# WIFI-RF433.net
KiCad netlist of a schematic drawn in EAGLE
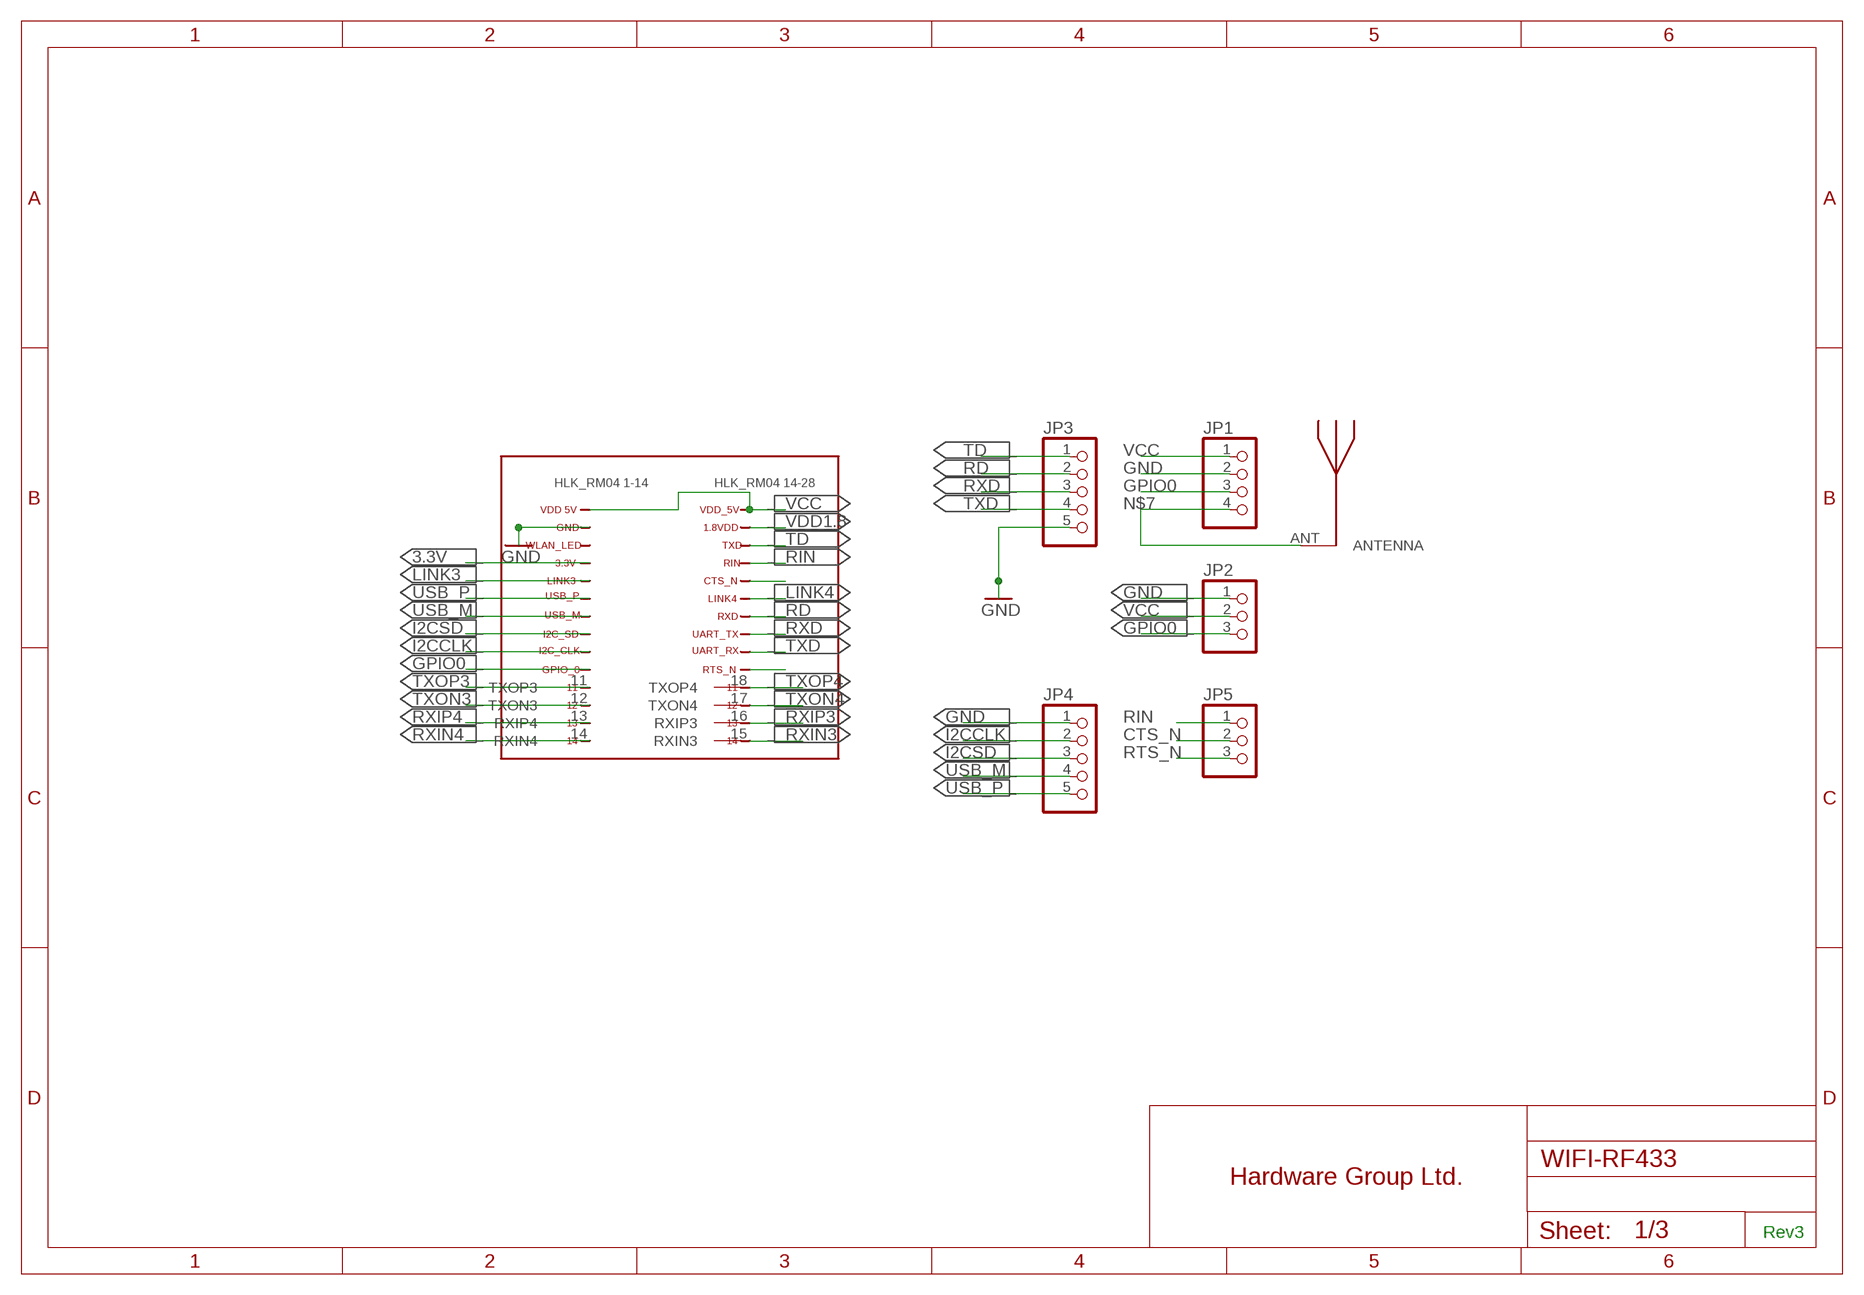
[diagram p0: schematic, sheet 1]
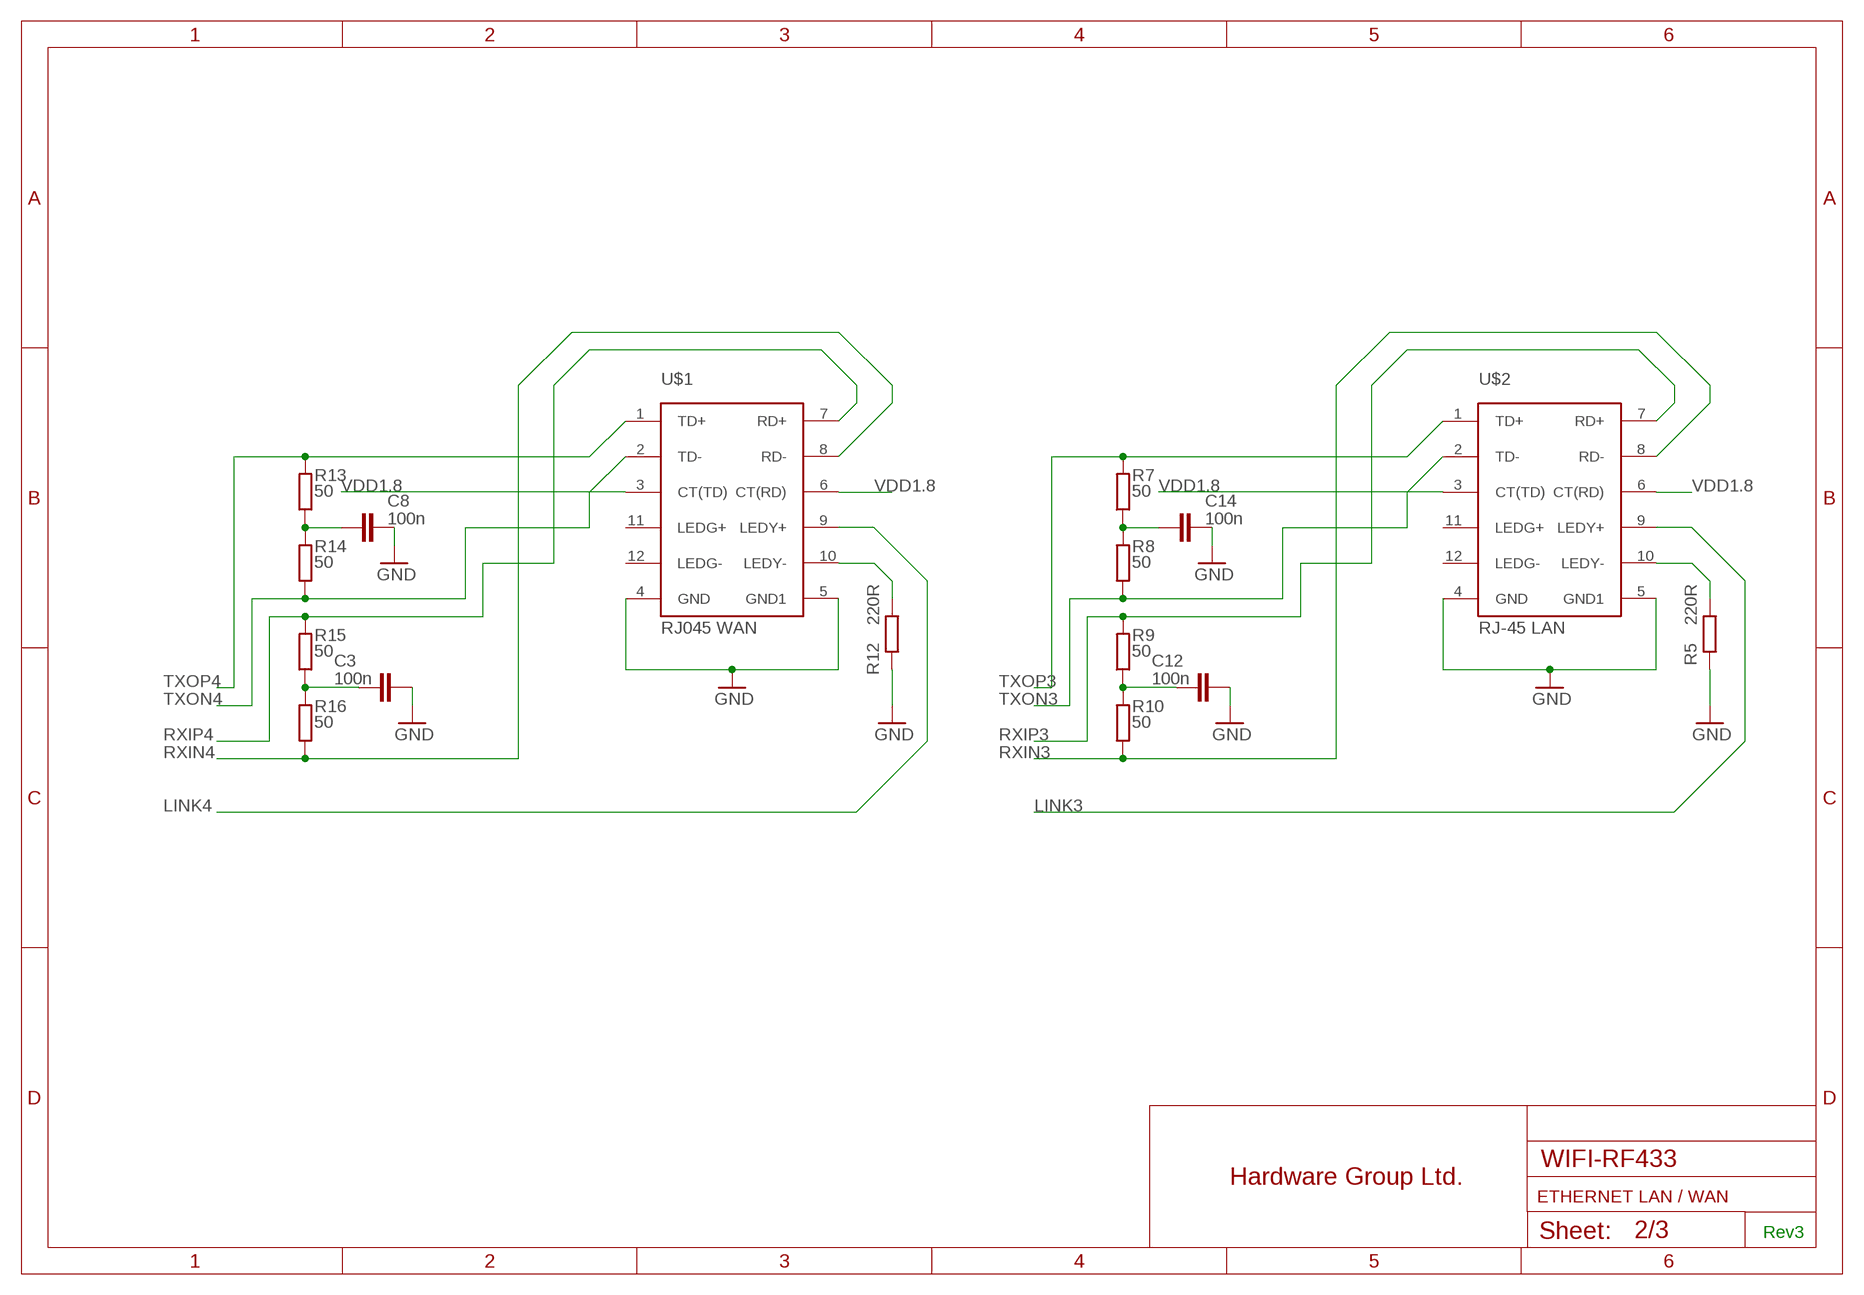
[diagram p1: schematic, sheet 2]
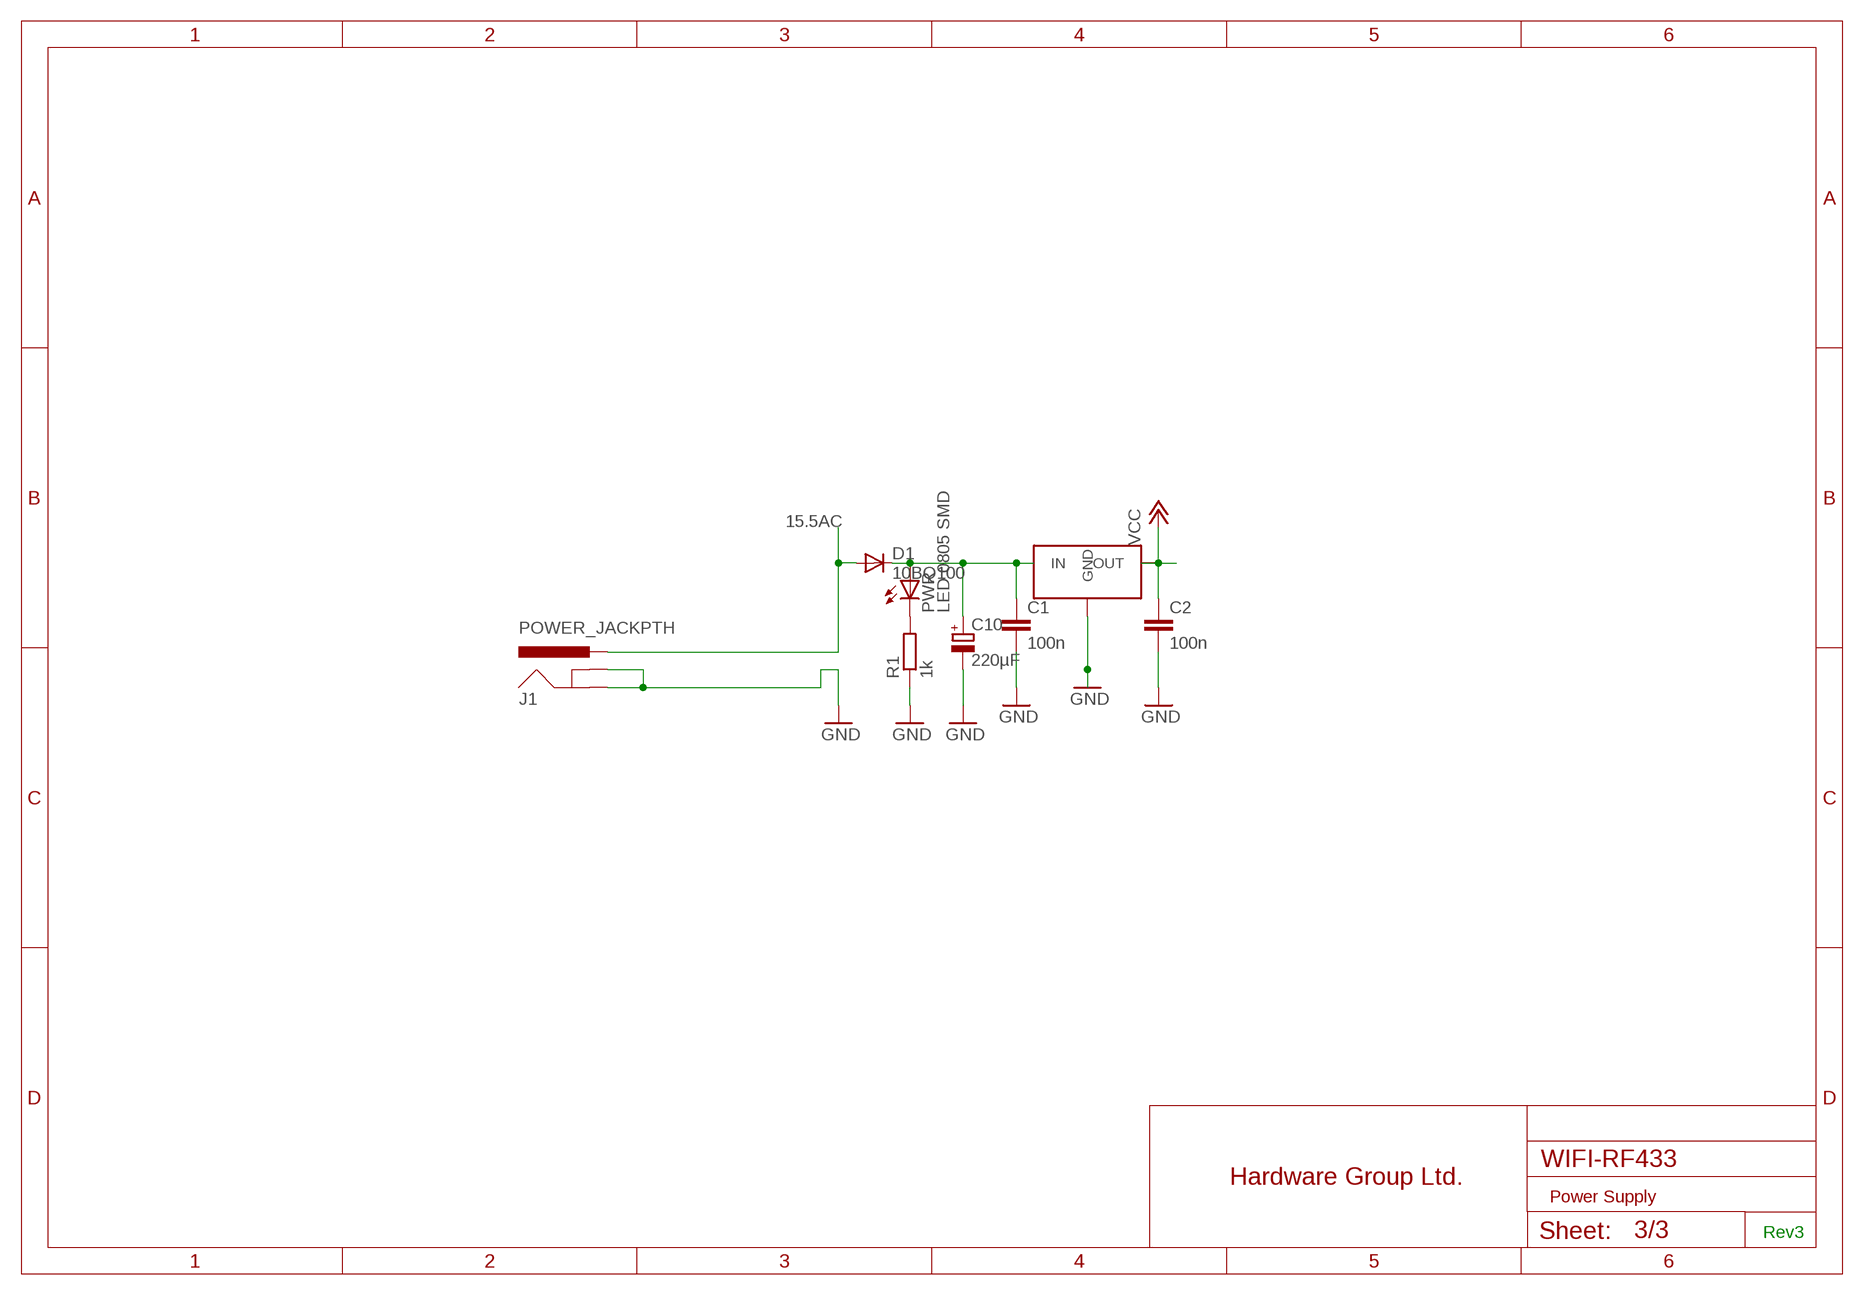
[diagram p2: schematic, sheet 3]

(export (version "E")
  (design (tool "Eeschema 10.0.6"))
  (components
    (comp (ref "C1")
      (value "100n")
      (footprint "eagle-import:C0805")
      (libsource (lib "eagle-import") (part "C-EUC0805"))
    )
    (comp (ref "C2")
      (value "100n")
      (footprint "eagle-import:C0805")
      (libsource (lib "eagle-import") (part "C-EUC0805"))
    )
    (comp (ref "C10")
      (value "220µF")
      (footprint "eagle-import:E3,5-8")
      (libsource (lib "eagle-import") (part "CPOL-EUE3.5-8"))
    )
    (comp (ref "D1")
      (value "10BQ100")
      (footprint "eagle-import:SMB")
      (libsource (lib "eagle-import") (part "DIODE-SMB"))
    )
    (comp (ref "J1")
      (value "POWER_JACKPTH")
      (footprint "eagle-import:POWER_JACK_PTH")
      (libsource (lib "eagle-import") (part "POWER_JACKPTH"))
    )
    (comp (ref "PWR")
      (value "LED 0805 SMD")
      (footprint "eagle-import:CHIP-LED0805")
      (libsource (lib "eagle-import") (part "LEDCHIP-LED0805"))
    )
    (comp (ref "R1")
      (value "1k")
      (footprint "eagle-import:M0805")
      (libsource (lib "eagle-import") (part "R-EU_M0805"))
    )
    (comp (ref "U$3")
      (value "VREG-7805-DPAK2")
      (footprint "eagle-import:VREG-7805-DPAK2")
      (libsource (lib "eagle-import") (part "VREG-7805-DPAK2"))
    )
    (comp (ref "JP1")
      (value "PINHD-1X4")
      (footprint "eagle-import:1X04")
      (libsource (lib "eagle-import") (part "PINHD-1X4"))
    )
    (comp (ref "JP2")
      (value "PINHD-1X3")
      (footprint "eagle-import:1X03")
      (libsource (lib "eagle-import") (part "PINHD-1X3"))
    )
    (comp (ref "JP3")
      (value "PINHD-1X5")
      (footprint "eagle-import:1X05")
      (libsource (lib "eagle-import") (part "PINHD-1X5"))
    )
    (comp (ref "JP4")
      (value "PINHD-1X5")
      (footprint "eagle-import:1X05")
      (libsource (lib "eagle-import") (part "PINHD-1X5"))
    )
    (comp (ref "JP5")
      (value "PINHD-1X3")
      (footprint "eagle-import:1X03")
      (libsource (lib "eagle-import") (part "PINHD-1X3"))
    )
    (comp (ref "U$4")
      (value "433MHZ")
      (footprint "eagle-import:433MHZ")
      (libsource (lib "eagle-import") (part "433MHZ"))
    )
    (comp (ref "U$8")
      (value "1X10")
      (footprint "eagle-import:1X10")
      (libsource (lib "eagle-import") (part "1X10"))
    )
    (comp (ref "C3")
      (value "100n")
      (footprint "eagle-import:C0805")
      (libsource (lib "eagle-import") (part "C-EUC0805"))
    )
    (comp (ref "C8")
      (value "100n")
      (footprint "eagle-import:C0805")
      (libsource (lib "eagle-import") (part "C-EUC0805"))
    )
    (comp (ref "C12")
      (value "100n")
      (footprint "eagle-import:C0805")
      (libsource (lib "eagle-import") (part "C-EUC0805"))
    )
    (comp (ref "C14")
      (value "100n")
      (footprint "eagle-import:C0805")
      (libsource (lib "eagle-import") (part "C-EUC0805"))
    )
    (comp (ref "R5")
      (value "220R")
      (footprint "eagle-import:R0805")
      (libsource (lib "eagle-import") (part "R-EU_R0805"))
    )
    (comp (ref "R7")
      (value "50")
      (footprint "eagle-import:R0805")
      (libsource (lib "eagle-import") (part "R-EU_R0805"))
    )
    (comp (ref "R8")
      (value "50")
      (footprint "eagle-import:R0805")
      (libsource (lib "eagle-import") (part "R-EU_R0805"))
    )
    (comp (ref "R9")
      (value "50")
      (footprint "eagle-import:R0805")
      (libsource (lib "eagle-import") (part "R-EU_R0805"))
    )
    (comp (ref "R10")
      (value "50")
      (footprint "eagle-import:R0805")
      (libsource (lib "eagle-import") (part "R-EU_R0805"))
    )
    (comp (ref "R12")
      (value "220R")
      (footprint "eagle-import:R0805")
      (libsource (lib "eagle-import") (part "R-EU_R0805"))
    )
    (comp (ref "R13")
      (value "50")
      (footprint "eagle-import:R0805")
      (libsource (lib "eagle-import") (part "R-EU_R0805"))
    )
    (comp (ref "R14")
      (value "50")
      (footprint "eagle-import:R0805")
      (libsource (lib "eagle-import") (part "R-EU_R0805"))
    )
    (comp (ref "R15")
      (value "50")
      (footprint "eagle-import:R0805")
      (libsource (lib "eagle-import") (part "R-EU_R0805"))
    )
    (comp (ref "R16")
      (value "50")
      (footprint "eagle-import:R0805")
      (libsource (lib "eagle-import") (part "R-EU_R0805"))
    )
    (comp (ref "U$1")
      (value "RJ045 WAN")
      (footprint "eagle-import:MAGJACK")
      (libsource (lib "eagle-import") (part "MAGJACKRJ45"))
    )
    (comp (ref "U$2")
      (value "RJ-45 LAN")
      (footprint "eagle-import:MAGJACK")
      (libsource (lib "eagle-import") (part "MAGJACKRJ45"))
    )
  )
  (nets
    (net (code "1") (name "3.3V") (class "Default")
      (node (ref "U$8") (pin "4") (pinfunction "3.3VDD_4") (pintype "bidirectional"))
    )
    (net (code "2") (name "15.5AC") (class "Default")
      (node (ref "D1") (pin "A") (pinfunction "A_A") (pintype "passive"))
      (node (ref "J1") (pin "PWR") (pinfunction "PWR_PWR") (pintype "bidirectional"))
    )
    (net (code "3") (name "CTS_N") (class "Default")
      (node (ref "JP5") (pin "2") (pinfunction "2_2") (pintype "passive"))
      (node (ref "U$8") (pin "24") (pinfunction "CTS_N_24") (pintype "bidirectional"))
    )
    (net (code "4") (name "GND") (class "Default")
      (node (ref "C1") (pin "2") (pinfunction "2_2") (pintype "passive"))
      (node (ref "C10") (pin "-") (pinfunction "-_-") (pintype "passive"))
      (node (ref "C12") (pin "2") (pinfunction "2_2") (pintype "passive"))
      (node (ref "C14") (pin "2") (pinfunction "2_2") (pintype "passive"))
      (node (ref "C2") (pin "2") (pinfunction "2_2") (pintype "passive"))
      (node (ref "C3") (pin "2") (pinfunction "2_2") (pintype "passive"))
      (node (ref "C8") (pin "2") (pinfunction "2_2") (pintype "passive"))
      (node (ref "J1") (pin "GND") (pinfunction "GND_GND") (pintype "bidirectional"))
      (node (ref "J1") (pin "GNDBREAK") (pinfunction "GNDBREAK_GNDBREAK") (pintype "bidirectional"))
      (node (ref "JP1") (pin "2") (pinfunction "2_2") (pintype "passive"))
      (node (ref "JP2") (pin "1") (pinfunction "1_1") (pintype "passive"))
      (node (ref "JP3") (pin "5") (pinfunction "5_5") (pintype "passive"))
      (node (ref "JP4") (pin "1") (pinfunction "1_1") (pintype "passive"))
      (node (ref "R1") (pin "1") (pinfunction "1_1") (pintype "passive"))
      (node (ref "R12") (pin "1") (pinfunction "1_1") (pintype "passive"))
      (node (ref "R5") (pin "1") (pinfunction "1_1") (pintype "passive"))
      (node (ref "U$1") (pin "4") (pinfunction "GND_4") (pintype "power_in"))
      (node (ref "U$1") (pin "5") (pinfunction "GND1_5") (pintype "power_in"))
      (node (ref "U$2") (pin "4") (pinfunction "GND_4") (pintype "power_in"))
      (node (ref "U$2") (pin "5") (pinfunction "GND1_5") (pintype "power_in"))
      (node (ref "U$3") (pin "GND") (pinfunction "GND_GND") (pintype "bidirectional"))
      (node (ref "U$8") (pin "2") (pinfunction "GND_2") (pintype "bidirectional"))
    )
    (net (code "5") (name "GPIO0") (class "Default")
      (node (ref "JP1") (pin "3") (pinfunction "3_3") (pintype "passive"))
      (node (ref "JP2") (pin "3") (pinfunction "3_3") (pintype "passive"))
      (node (ref "U$8") (pin "10") (pinfunction "GPIO_0_10") (pintype "bidirectional"))
    )
    (net (code "6") (name "I2CCLK") (class "Default")
      (node (ref "JP4") (pin "2") (pinfunction "2_2") (pintype "passive"))
      (node (ref "U$8") (pin "9") (pinfunction "I2C_CLK_9") (pintype "bidirectional"))
    )
    (net (code "7") (name "I2CSD") (class "Default")
      (node (ref "JP4") (pin "3") (pinfunction "3_3") (pintype "passive"))
      (node (ref "U$8") (pin "8") (pinfunction "I2C_SD_8") (pintype "bidirectional"))
    )
    (net (code "8") (name "LINK3") (class "Default")
      (node (ref "U$2") (pin "9") (pinfunction "LEDY+_9") (pintype "bidirectional"))
      (node (ref "U$8") (pin "5") (pinfunction "LINK3_5") (pintype "bidirectional"))
    )
    (net (code "9") (name "LINK4") (class "Default")
      (node (ref "U$1") (pin "9") (pinfunction "LEDY+_9") (pintype "bidirectional"))
      (node (ref "U$8") (pin "23") (pinfunction "LINK4_23") (pintype "bidirectional"))
    )
    (net (code "10") (name "N$7") (class "Default")
      (node (ref "JP1") (pin "4") (pinfunction "4_4") (pintype "passive"))
      (node (ref "U$4") (pin "ANT") (pinfunction "ANTENNA_ANT") (pintype "output"))
    )
    (net (code "11") (name "Net-(C3-Pad1)") (class "Default")
      (node (ref "C3") (pin "1") (pinfunction "1_1") (pintype "passive"))
      (node (ref "R15") (pin "1") (pinfunction "1_1") (pintype "passive"))
      (node (ref "R16") (pin "2") (pinfunction "2_2") (pintype "passive"))
    )
    (net (code "12") (name "Net-(C8-Pad1)") (class "Default")
      (node (ref "C8") (pin "1") (pinfunction "1_1") (pintype "passive"))
      (node (ref "R13") (pin "1") (pinfunction "1_1") (pintype "passive"))
      (node (ref "R14") (pin "2") (pinfunction "2_2") (pintype "passive"))
    )
    (net (code "13") (name "Net-(C12-Pad1)") (class "Default")
      (node (ref "C12") (pin "1") (pinfunction "1_1") (pintype "passive"))
      (node (ref "R10") (pin "2") (pinfunction "2_2") (pintype "passive"))
      (node (ref "R9") (pin "1") (pinfunction "1_1") (pintype "passive"))
    )
    (net (code "14") (name "Net-(C14-Pad1)") (class "Default")
      (node (ref "C14") (pin "1") (pinfunction "1_1") (pintype "passive"))
      (node (ref "R7") (pin "1") (pinfunction "1_1") (pintype "passive"))
      (node (ref "R8") (pin "2") (pinfunction "2_2") (pintype "passive"))
    )
    (net (code "15") (name "Net-(PWR-PadC)") (class "Default")
      (node (ref "PWR") (pin "C") (pinfunction "C_C") (pintype "passive"))
      (node (ref "R1") (pin "2") (pinfunction "2_2") (pintype "passive"))
    )
    (net (code "16") (name "Net-(U$1-LEDY-)") (class "Default")
      (node (ref "R12") (pin "2") (pinfunction "2_2") (pintype "passive"))
      (node (ref "U$1") (pin "10") (pinfunction "LEDY-_10") (pintype "bidirectional"))
    )
    (net (code "17") (name "Net-(U$2-LEDY-)") (class "Default")
      (node (ref "R5") (pin "2") (pinfunction "2_2") (pintype "passive"))
      (node (ref "U$2") (pin "10") (pinfunction "LEDY-_10") (pintype "bidirectional"))
    )
    (net (code "18") (name "Net-(U$3-IN)") (class "Default")
      (node (ref "C1") (pin "1") (pinfunction "1_1") (pintype "passive"))
      (node (ref "C10") (pin "+") (pinfunction "+_+") (pintype "passive"))
      (node (ref "D1") (pin "C") (pinfunction "C_C") (pintype "passive"))
      (node (ref "PWR") (pin "A") (pinfunction "A_A") (pintype "passive"))
      (node (ref "U$3") (pin "VIN") (pinfunction "IN_VIN") (pintype "bidirectional"))
    )
    (net (code "19") (name "RD") (class "Default")
      (node (ref "JP3") (pin "2") (pinfunction "2_2") (pintype "passive"))
      (node (ref "U$8") (pin "22") (pinfunction "RXD_22") (pintype "bidirectional"))
    )
    (net (code "20") (name "RIN") (class "Default")
      (node (ref "JP5") (pin "1") (pinfunction "1_1") (pintype "passive"))
      (node (ref "U$8") (pin "25") (pinfunction "RIN_25") (pintype "bidirectional"))
    )
    (net (code "21") (name "RTS_N") (class "Default")
      (node (ref "JP5") (pin "3") (pinfunction "3_3") (pintype "passive"))
      (node (ref "U$8") (pin "19") (pinfunction "RTS_N_19") (pintype "bidirectional"))
    )
    (net (code "22") (name "RXD") (class "Default")
      (node (ref "JP3") (pin "3") (pinfunction "3_3") (pintype "passive"))
      (node (ref "U$8") (pin "21") (pinfunction "UART_TX_21") (pintype "bidirectional"))
    )
    (net (code "23") (name "RXIN3") (class "Default")
      (node (ref "R10") (pin "1") (pinfunction "1_1") (pintype "passive"))
      (node (ref "U$2") (pin "8") (pinfunction "RD-_8") (pintype "bidirectional"))
      (node (ref "U$8") (pin "15") (pinfunction "RXIN3_15") (pintype "bidirectional"))
    )
    (net (code "24") (name "RXIN4") (class "Default")
      (node (ref "R16") (pin "1") (pinfunction "1_1") (pintype "passive"))
      (node (ref "U$1") (pin "8") (pinfunction "RD-_8") (pintype "bidirectional"))
      (node (ref "U$8") (pin "14") (pinfunction "RXIN4_14") (pintype "bidirectional"))
    )
    (net (code "25") (name "RXIP3") (class "Default")
      (node (ref "R9") (pin "2") (pinfunction "2_2") (pintype "passive"))
      (node (ref "U$2") (pin "7") (pinfunction "RD+_7") (pintype "bidirectional"))
      (node (ref "U$8") (pin "16") (pinfunction "RXIP3_16") (pintype "bidirectional"))
    )
    (net (code "26") (name "RXIP4") (class "Default")
      (node (ref "R15") (pin "2") (pinfunction "2_2") (pintype "passive"))
      (node (ref "U$1") (pin "7") (pinfunction "RD+_7") (pintype "bidirectional"))
      (node (ref "U$8") (pin "13") (pinfunction "RXIP4_13") (pintype "bidirectional"))
    )
    (net (code "27") (name "TD") (class "Default")
      (node (ref "JP3") (pin "1") (pinfunction "1_1") (pintype "passive"))
      (node (ref "U$8") (pin "26") (pinfunction "TXD_26") (pintype "bidirectional"))
    )
    (net (code "28") (name "TXD") (class "Default")
      (node (ref "JP3") (pin "4") (pinfunction "4_4") (pintype "passive"))
      (node (ref "U$8") (pin "20") (pinfunction "UART_RX_20") (pintype "bidirectional"))
    )
    (net (code "29") (name "TXON3") (class "Default")
      (node (ref "R8") (pin "1") (pinfunction "1_1") (pintype "passive"))
      (node (ref "U$2") (pin "2") (pinfunction "TD-_2") (pintype "bidirectional"))
      (node (ref "U$8") (pin "12") (pinfunction "TXON3_12") (pintype "bidirectional"))
    )
    (net (code "30") (name "TXON4") (class "Default")
      (node (ref "R14") (pin "1") (pinfunction "1_1") (pintype "passive"))
      (node (ref "U$1") (pin "2") (pinfunction "TD-_2") (pintype "bidirectional"))
      (node (ref "U$8") (pin "17") (pinfunction "TXON4_17") (pintype "bidirectional"))
    )
    (net (code "31") (name "TXOP3") (class "Default")
      (node (ref "R7") (pin "2") (pinfunction "2_2") (pintype "passive"))
      (node (ref "U$2") (pin "1") (pinfunction "TD+_1") (pintype "bidirectional"))
      (node (ref "U$8") (pin "11") (pinfunction "TXOP3_11") (pintype "bidirectional"))
    )
    (net (code "32") (name "TXOP4") (class "Default")
      (node (ref "R13") (pin "2") (pinfunction "2_2") (pintype "passive"))
      (node (ref "U$1") (pin "1") (pinfunction "TD+_1") (pintype "bidirectional"))
      (node (ref "U$8") (pin "18") (pinfunction "TXOP4_18") (pintype "bidirectional"))
    )
    (net (code "33") (name "USB_M") (class "Default")
      (node (ref "JP4") (pin "4") (pinfunction "4_4") (pintype "passive"))
      (node (ref "U$8") (pin "7") (pinfunction "USB_M_7") (pintype "bidirectional"))
    )
    (net (code "34") (name "USB_P") (class "Default")
      (node (ref "JP4") (pin "5") (pinfunction "5_5") (pintype "passive"))
      (node (ref "U$8") (pin "6") (pinfunction "USB_P_6") (pintype "bidirectional"))
    )
    (net (code "35") (name "VCC") (class "Default")
      (node (ref "C2") (pin "1") (pinfunction "1_1") (pintype "passive"))
      (node (ref "JP1") (pin "1") (pinfunction "1_1") (pintype "passive"))
      (node (ref "JP2") (pin "2") (pinfunction "2_2") (pintype "passive"))
      (node (ref "U$3") (pin "VOUT") (pinfunction "OUT_VOUT") (pintype "bidirectional"))
      (node (ref "U$8") (pin "1") (pinfunction "VDD_5V_1") (pintype "bidirectional"))
      (node (ref "U$8") (pin "28") (pinfunction "VDD_5V__28") (pintype "bidirectional"))
    )
    (net (code "36") (name "VDD1.8") (class "Default")
      (node (ref "U$1") (pin "3") (pinfunction "CT(TD)_3") (pintype "bidirectional"))
      (node (ref "U$1") (pin "6") (pinfunction "CT(RD)_6") (pintype "bidirectional"))
      (node (ref "U$2") (pin "3") (pinfunction "CT(TD)_3") (pintype "bidirectional"))
      (node (ref "U$2") (pin "6") (pinfunction "CT(RD)_6") (pintype "bidirectional"))
      (node (ref "U$8") (pin "27") (pinfunction "1.8VDD_27") (pintype "bidirectional"))
    )
    (net (code "37") (name "unconnected-(U$1-LEDG+-Pad11)") (class "Default")
      (node (ref "U$1") (pin "11") (pinfunction "LEDG+_11") (pintype "bidirectional"))
    )
    (net (code "38") (name "unconnected-(U$1-LEDG--Pad12)") (class "Default")
      (node (ref "U$1") (pin "12") (pinfunction "LEDG-_12") (pintype "bidirectional"))
    )
    (net (code "39") (name "unconnected-(U$2-LEDG+-Pad11)") (class "Default")
      (node (ref "U$2") (pin "11") (pinfunction "LEDG+_11") (pintype "bidirectional"))
    )
    (net (code "40") (name "unconnected-(U$2-LEDG--Pad12)") (class "Default")
      (node (ref "U$2") (pin "12") (pinfunction "LEDG-_12") (pintype "bidirectional"))
    )
    (net (code "41") (name "unconnected-(U$8-WLAN_LED-Pad3)") (class "Default")
      (node (ref "U$8") (pin "3") (pinfunction "WLAN_LED_3") (pintype "bidirectional"))
    )
  )
)
